# SPI.net
KiCad netlist of a schematic drawn in Altium Designer
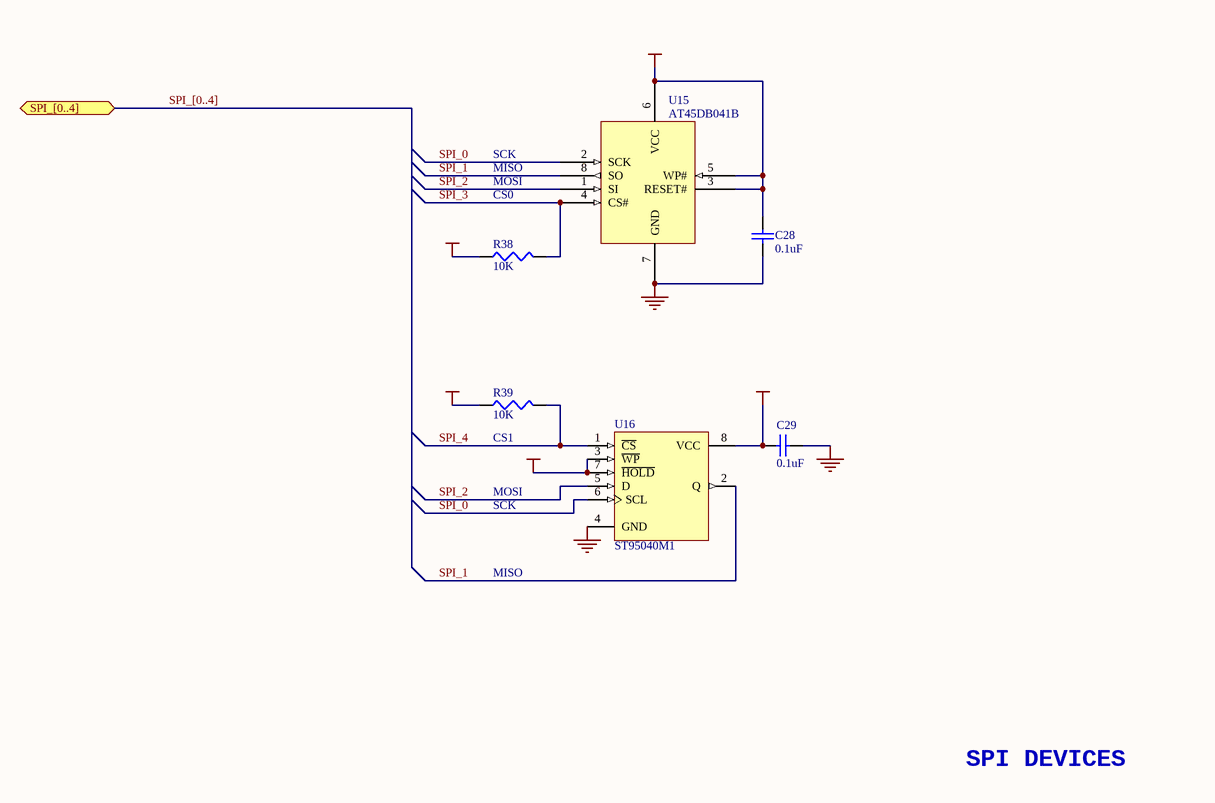
[diagram p0: SPI.SCHDOC]

(export (version "E")
  (design (tool "Eeschema 10.0.6"))
  (components
    (comp (ref "C28")
      (value "0.1uF")
      (footprint "_0805")
      (description "Capacitor (Semiconductor SIM Model)")
      (fields (field (name "Comment") "Cap Semi") (field (name "PUBLISHER") "Altium Limited"))
      (libsource (lib "Miscellaneous Devices") (part "Cap Semi"))
    )
    (comp (ref "C29")
      (value "0.1uF")
      (footprint "_0805")
      (description "Capacitor (Semiconductor SIM Model)")
      (fields (field (name "Comment") "Cap Semi") (field (name "PUBLISHER") "Altium Limited"))
      (libsource (lib "Miscellaneous Devices") (part "Cap Semi"))
    )
    (comp (ref "R38")
      (value "10K")
      (footprint "_0805")
      (description "Resistor")
      (fields (field (name "Comment") "Res3") (field (name "PUBLISHER") "Altium Limited"))
      (libsource (lib "Miscellaneous Devices") (part "Res3"))
    )
    (comp (ref "R39")
      (value "10K")
      (footprint "_0805")
      (description "Resistor")
      (fields (field (name "Comment") "Res3") (field (name "PUBLISHER") "Altium Limited"))
      (libsource (lib "Miscellaneous Devices") (part "Res3"))
    )
    (comp (ref "U15")
      (value "AT45DB041B")
      (footprint "SO-G8/E4.1")
      (description "4 Megabit DataFlash Memory")
      (libsource (lib "Vending") (part "AT45DB041B"))
    )
    (comp (ref "U16")
      (value "ST95040M1")
      (footprint "SOP8")
      (description "4K Serial SPI EEPROM with Positive Clock Strobe")
      (fields (field (name "PUBLISHER") "Altium Limited"))
      (libsource (lib "ST Memory EEPROM Serial") (part "ST95040M1"))
    )
  )
  (nets
    (net (code "1") (name "/SPI_0") (class "Default")
      (node (ref "U15") (pin "2") (pinfunction "SCK_2") (pintype "input"))
      (node (ref "U16") (pin "6") (pinfunction "SCL_6") (pintype "input"))
    )
    (net (code "2") (name "/SPI_1") (class "Default")
      (node (ref "U15") (pin "8") (pinfunction "SO_8") (pintype "output"))
      (node (ref "U16") (pin "2") (pinfunction "Q_2") (pintype "output"))
    )
    (net (code "3") (name "/SPI_2") (class "Default")
      (node (ref "U15") (pin "1") (pinfunction "SI_1") (pintype "input"))
      (node (ref "U16") (pin "5") (pinfunction "D_5") (pintype "input"))
    )
    (net (code "4") (name "/SPI_3") (class "Default")
      (node (ref "R38") (pin "2") (pinfunction "2_2") (pintype "passive"))
      (node (ref "U15") (pin "4") (pinfunction "CS#_4") (pintype "input"))
    )
    (net (code "5") (name "/SPI_4") (class "Default")
      (node (ref "R39") (pin "2") (pinfunction "2_2") (pintype "passive"))
      (node (ref "U16") (pin "1") (pinfunction "~{CS}_1") (pintype "input"))
    )
    (net (code "7") (name "GND") (class "Default")
      (node (ref "C28") (pin "2") (pinfunction "2_2") (pintype "passive"))
      (node (ref "C29") (pin "2") (pinfunction "2_2") (pintype "passive"))
      (node (ref "U15") (pin "7") (pinfunction "GND_7") (pintype "power_in"))
      (node (ref "U16") (pin "4") (pinfunction "GND_4") (pintype "power_in"))
    )
    (net (code "8") (name "VCC_3V") (class "Default")
      (node (ref "C28") (pin "1") (pinfunction "1_1") (pintype "passive"))
      (node (ref "C29") (pin "1") (pinfunction "1_1") (pintype "passive"))
      (node (ref "R38") (pin "1") (pinfunction "1_1") (pintype "passive"))
      (node (ref "R39") (pin "1") (pinfunction "1_1") (pintype "passive"))
      (node (ref "U15") (pin "3") (pinfunction "RESET#_3") (pintype "passive"))
      (node (ref "U15") (pin "5") (pinfunction "WP#_5") (pintype "input"))
      (node (ref "U15") (pin "6") (pinfunction "VCC_6") (pintype "power_in"))
      (node (ref "U16") (pin "3") (pinfunction "~{WP}_3") (pintype "input"))
      (node (ref "U16") (pin "7") (pinfunction "~{HOLD}_7") (pintype "input"))
      (node (ref "U16") (pin "8") (pinfunction "VCC_8") (pintype "power_in"))
    )
  )
)
